# MP3_PCB.net
KiCad netlist of a schematic drawn in Altium Designer
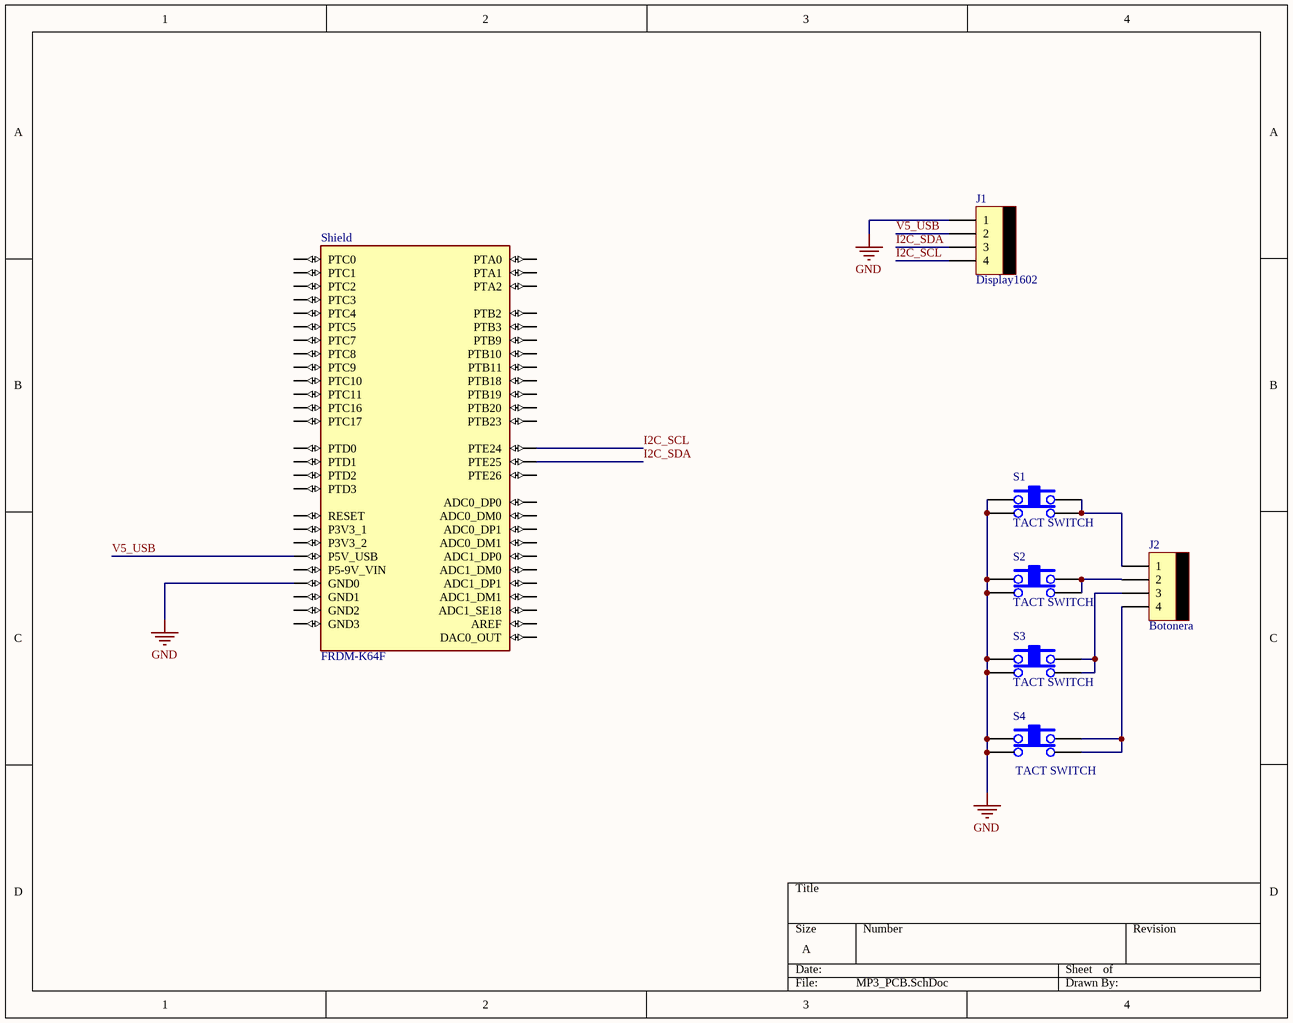
[diagram p0: MP3_PCB.SchDoc]

(export (version "E")
  (design (tool "Eeschema 10.0.6"))
  (components
    (comp (ref "J1") (value "Display1602") (footprint "MOLEX4") (libsource (lib "LIBEBAL") (part "MOLEX4")))
    (comp (ref "J2") (value "Botonera") (footprint "MOLEX4") (libsource (lib "LIBEBAL") (part "MOLEX4")))
    (comp (ref "S1")
      (value "TACT SWITCH")
      (footprint "TACTSWITCH")
      (libsource (lib "LIBEBAL") (part "TACT SWITCH"))
    )
    (comp (ref "S2")
      (value "TACT SWITCH")
      (footprint "TACTSWITCH")
      (libsource (lib "LIBEBAL") (part "TACT SWITCH"))
    )
    (comp (ref "S3")
      (value "TACT SWITCH")
      (footprint "TACTSWITCH")
      (libsource (lib "LIBEBAL") (part "TACT SWITCH"))
    )
    (comp (ref "S4")
      (value "TACT SWITCH")
      (footprint "TACTSWITCH")
      (libsource (lib "LIBEBAL") (part "TACT SWITCH"))
    )
    (comp (ref "Shield")
      (value "FRDM-K64F")
      (footprint "FRDM-K64F")
      (fields (field (name "MF") "NXP USA"))
      (libsource (lib "FRDM-K64F") (part "FRDM-K64F"))
    )
  )
  (nets
    (net (code "1") (name "/I2C_SCL") (class "Default")
      (node (ref "J1") (pin "4") (pinfunction "4_4") (pintype "passive"))
      (node (ref "Shield") (pin "J2-20") (pinfunction "PTE24_J2-20") (pintype "bidirectional"))
    )
    (net (code "2") (name "/I2C_SDA") (class "Default")
      (node (ref "J1") (pin "3") (pinfunction "3_3") (pintype "passive"))
      (node (ref "Shield") (pin "J2-18") (pinfunction "PTE25_J2-18") (pintype "bidirectional"))
    )
    (net (code "3") (name "/V5_USB") (class "Default")
      (node (ref "J1") (pin "2") (pinfunction "2_2") (pintype "passive"))
      (node (ref "Shield") (pin "J3-10") (pinfunction "P5V_USB_J3-10") (pintype "bidirectional"))
    )
    (net (code "4") (name "GND") (class "Default")
      (node (ref "J1") (pin "1") (pinfunction "1_1") (pintype "passive"))
      (node (ref "S1") (pin "1") (pinfunction "1_1") (pintype "passive"))
      (node (ref "S1") (pin "2") (pinfunction "2_2") (pintype "passive"))
      (node (ref "S2") (pin "1") (pinfunction "1_1") (pintype "passive"))
      (node (ref "S2") (pin "2") (pinfunction "2_2") (pintype "passive"))
      (node (ref "S3") (pin "1") (pinfunction "1_1") (pintype "passive"))
      (node (ref "S3") (pin "2") (pinfunction "2_2") (pintype "passive"))
      (node (ref "S4") (pin "1") (pinfunction "1_1") (pintype "passive"))
      (node (ref "S4") (pin "2") (pinfunction "2_2") (pintype "passive"))
      (node (ref "Shield") (pin "J2-3") (pinfunction "GND0_J2-3") (pintype "bidirectional"))
    )
    (net (code "5") (name "Net-(J2-Pad1)") (class "Default")
      (node (ref "J2") (pin "1") (pinfunction "1_1") (pintype "passive"))
      (node (ref "S1") (pin "3") (pinfunction "3_3") (pintype "passive"))
      (node (ref "S1") (pin "4") (pinfunction "4_4") (pintype "passive"))
    )
    (net (code "6") (name "Net-(J2-Pad2)") (class "Default")
      (node (ref "J2") (pin "2") (pinfunction "2_2") (pintype "passive"))
      (node (ref "S2") (pin "3") (pinfunction "3_3") (pintype "passive"))
      (node (ref "S2") (pin "4") (pinfunction "4_4") (pintype "passive"))
    )
    (net (code "7") (name "Net-(J2-Pad3)") (class "Default")
      (node (ref "J2") (pin "3") (pinfunction "3_3") (pintype "passive"))
      (node (ref "S3") (pin "3") (pinfunction "3_3") (pintype "passive"))
      (node (ref "S3") (pin "4") (pinfunction "4_4") (pintype "passive"))
    )
    (net (code "8") (name "Net-(J2-Pad4)") (class "Default")
      (node (ref "J2") (pin "4") (pinfunction "4_4") (pintype "passive"))
      (node (ref "S4") (pin "3") (pinfunction "3_3") (pintype "passive"))
      (node (ref "S4") (pin "4") (pinfunction "4_4") (pintype "passive"))
    )
    (net (code "9") (name "unconnected-(Shield-ADC0_DM0-PadJ2-7)") (class "Default")
      (node (ref "Shield") (pin "J2-7") (pinfunction "ADC0_DM0_J2-7") (pintype "bidirectional"))
    )
    (net (code "10") (name "unconnected-(Shield-ADC0_DM1-PadJ4-3)") (class "Default")
      (node (ref "Shield") (pin "J4-3") (pinfunction "ADC0_DM1_J4-3") (pintype "bidirectional"))
    )
    (net (code "11") (name "unconnected-(Shield-ADC0_DP0-PadJ2-5)") (class "Default")
      (node (ref "Shield") (pin "J2-5") (pinfunction "ADC0_DP0_J2-5") (pintype "bidirectional"))
    )
    (net (code "12") (name "unconnected-(Shield-ADC0_DP1-PadJ4-1)") (class "Default")
      (node (ref "Shield") (pin "J4-1") (pinfunction "ADC0_DP1_J4-1") (pintype "bidirectional"))
    )
    (net (code "13") (name "unconnected-(Shield-ADC1_DM0-PadJ2-13)") (class "Default")
      (node (ref "Shield") (pin "J2-13") (pinfunction "ADC1_DM0_J2-13") (pintype "bidirectional"))
    )
    (net (code "14") (name "unconnected-(Shield-ADC1_DM1-PadJ4-7)") (class "Default")
      (node (ref "Shield") (pin "J4-7") (pinfunction "ADC1_DM1_J4-7") (pintype "bidirectional"))
    )
    (net (code "15") (name "unconnected-(Shield-ADC1_DP0-PadJ2-11)") (class "Default")
      (node (ref "Shield") (pin "J2-11") (pinfunction "ADC1_DP0_J2-11") (pintype "bidirectional"))
    )
    (net (code "16") (name "unconnected-(Shield-ADC1_DP1-PadJ4-5)") (class "Default")
      (node (ref "Shield") (pin "J4-5") (pinfunction "ADC1_DP1_J4-5") (pintype "bidirectional"))
    )
    (net (code "17") (name "unconnected-(Shield-ADC1_SE18-PadJ2-17)") (class "Default")
      (node (ref "Shield") (pin "J2-17") (pinfunction "ADC1_SE18_J2-17") (pintype "bidirectional"))
    )
    (net (code "18") (name "unconnected-(Shield-AREF-PadJ2-16)") (class "Default")
      (node (ref "Shield") (pin "J2-16") (pinfunction "AREF_J2-16") (pintype "bidirectional"))
    )
    (net (code "19") (name "unconnected-(Shield-DAC0_OUT-PadJ4-11)") (class "Default")
      (node (ref "Shield") (pin "J4-11") (pinfunction "DAC0_OUT_J4-11") (pintype "bidirectional"))
    )
    (net (code "20") (name "unconnected-(Shield-GND1-PadJ2-14)") (class "Default")
      (node (ref "Shield") (pin "J2-14") (pinfunction "GND1_J2-14") (pintype "bidirectional"))
    )
    (net (code "21") (name "unconnected-(Shield-GND2-PadJ3-12)") (class "Default")
      (node (ref "Shield") (pin "J3-12") (pinfunction "GND2_J3-12") (pintype "bidirectional"))
    )
    (net (code "22") (name "unconnected-(Shield-GND3-PadJ3-14)") (class "Default")
      (node (ref "Shield") (pin "J3-14") (pinfunction "GND3_J3-14") (pintype "bidirectional"))
    )
    (net (code "23") (name "unconnected-(Shield-P3V3_1-PadJ3-4)") (class "Default")
      (node (ref "Shield") (pin "J3-4") (pinfunction "P3V3_1_J3-4") (pintype "bidirectional"))
    )
    (net (code "24") (name "unconnected-(Shield-P3V3_2-PadJ3-8)") (class "Default")
      (node (ref "Shield") (pin "J3-8") (pinfunction "P3V3_2_J3-8") (pintype "bidirectional"))
    )
    (net (code "25") (name "unconnected-(Shield-P5-9V_VIN-PadJ3-16)") (class "Default")
      (node (ref "Shield") (pin "J3-16") (pinfunction "P5-9V_VIN_J3-16") (pintype "bidirectional"))
    )
    (net (code "26") (name "unconnected-(Shield-PTA0-PadJ2-2)") (class "Default")
      (node (ref "Shield") (pin "J2-2") (pinfunction "PTA0_J2-2") (pintype "bidirectional"))
    )
    (net (code "27") (name "unconnected-(Shield-PTA1-PadJ1-8)") (class "Default")
      (node (ref "Shield") (pin "J1-8") (pinfunction "PTA1_J1-8") (pintype "bidirectional"))
    )
    (net (code "28") (name "unconnected-(Shield-PTA2-PadJ1-12)") (class "Default")
      (node (ref "Shield") (pin "J1-12") (pinfunction "PTA2_J1-12") (pintype "bidirectional"))
    )
    (net (code "29") (name "unconnected-(Shield-PTB2-PadJ4-2)") (class "Default")
      (node (ref "Shield") (pin "J4-2") (pinfunction "PTB2_J4-2") (pintype "bidirectional"))
    )
    (net (code "30") (name "unconnected-(Shield-PTB3-PadJ4-4)") (class "Default")
      (node (ref "Shield") (pin "J4-4") (pinfunction "PTB3_J4-4") (pintype "bidirectional"))
    )
    (net (code "31") (name "unconnected-(Shield-PTB9-PadJ1-6)") (class "Default")
      (node (ref "Shield") (pin "J1-6") (pinfunction "PTB9_J1-6") (pintype "bidirectional"))
    )
    (net (code "32") (name "unconnected-(Shield-PTB10-PadJ4-6)") (class "Default")
      (node (ref "Shield") (pin "J4-6") (pinfunction "PTB10_J4-6") (pintype "bidirectional"))
    )
    (net (code "33") (name "unconnected-(Shield-PTB11-PadJ4-8)") (class "Default")
      (node (ref "Shield") (pin "J4-8") (pinfunction "PTB11_J4-8") (pintype "bidirectional"))
    )
    (net (code "34") (name "unconnected-(Shield-PTB18-PadJ1-1)") (class "Default")
      (node (ref "Shield") (pin "J1-1") (pinfunction "PTB18_J1-1") (pintype "bidirectional"))
    )
    (net (code "35") (name "unconnected-(Shield-PTB19-PadJ1-3)") (class "Default")
      (node (ref "Shield") (pin "J1-3") (pinfunction "PTB19_J1-3") (pintype "bidirectional"))
    )
    (net (code "36") (name "unconnected-(Shield-PTB20-PadJ4-9)") (class "Default")
      (node (ref "Shield") (pin "J4-9") (pinfunction "PTB20_J4-9") (pintype "bidirectional"))
    )
    (net (code "37") (name "unconnected-(Shield-PTB23-PadJ1-10)") (class "Default")
      (node (ref "Shield") (pin "J1-10") (pinfunction "PTB23_J1-10") (pintype "bidirectional"))
    )
    (net (code "38") (name "unconnected-(Shield-PTC0-PadJ1-11)") (class "Default")
      (node (ref "Shield") (pin "J1-11") (pinfunction "PTC0_J1-11") (pintype "bidirectional"))
    )
    (net (code "39") (name "unconnected-(Shield-PTC1-PadJ1-5)") (class "Default")
      (node (ref "Shield") (pin "J1-5") (pinfunction "PTC1_J1-5") (pintype "bidirectional"))
    )
    (net (code "40") (name "unconnected-(Shield-PTC2-PadJ1-14)") (class "Default")
      (node (ref "Shield") (pin "J1-14") (pinfunction "PTC2_J1-14") (pintype "bidirectional"))
    )
    (net (code "41") (name "unconnected-(Shield-PTC3-PadJ1-16)") (class "Default")
      (node (ref "Shield") (pin "J1-16") (pinfunction "PTC3_J1-16") (pintype "bidirectional"))
    )
    (net (code "42") (name "unconnected-(Shield-PTC4-PadJ2-4)") (class "Default")
      (node (ref "Shield") (pin "J2-4") (pinfunction "PTC4_J2-4") (pintype "bidirectional"))
    )
    (net (code "43") (name "unconnected-(Shield-PTC5-PadJ1-15)") (class "Default")
      (node (ref "Shield") (pin "J1-15") (pinfunction "PTC5_J1-15") (pintype "bidirectional"))
    )
    (net (code "44") (name "unconnected-(Shield-PTC7-PadJ1-13)") (class "Default")
      (node (ref "Shield") (pin "J1-13") (pinfunction "PTC7_J1-13") (pintype "bidirectional"))
    )
    (net (code "45") (name "unconnected-(Shield-PTC8-PadJ1-7)") (class "Default")
      (node (ref "Shield") (pin "J1-7") (pinfunction "PTC8_J1-7") (pintype "bidirectional"))
    )
    (net (code "46") (name "unconnected-(Shield-PTC9-PadJ1-9)") (class "Default")
      (node (ref "Shield") (pin "J1-9") (pinfunction "PTC9_J1-9") (pintype "bidirectional"))
    )
    (net (code "47") (name "unconnected-(Shield-PTC10-PadJ4-12)") (class "Default")
      (node (ref "Shield") (pin "J4-12") (pinfunction "PTC10_J4-12") (pintype "bidirectional"))
    )
    (net (code "48") (name "unconnected-(Shield-PTC11-PadJ4-10)") (class "Default")
      (node (ref "Shield") (pin "J4-10") (pinfunction "PTC11_J4-10") (pintype "bidirectional"))
    )
    (net (code "49") (name "unconnected-(Shield-PTC16-PadJ1-2)") (class "Default")
      (node (ref "Shield") (pin "J1-2") (pinfunction "PTC16_J1-2") (pintype "bidirectional"))
    )
    (net (code "50") (name "unconnected-(Shield-PTC17-PadJ1-4)") (class "Default")
      (node (ref "Shield") (pin "J1-4") (pinfunction "PTC17_J1-4") (pintype "bidirectional"))
    )
    (net (code "51") (name "unconnected-(Shield-PTD0-PadJ2-6)") (class "Default")
      (node (ref "Shield") (pin "J2-6") (pinfunction "PTD0_J2-6") (pintype "bidirectional"))
    )
    (net (code "52") (name "unconnected-(Shield-PTD1-PadJ2-12)") (class "Default")
      (node (ref "Shield") (pin "J2-12") (pinfunction "PTD1_J2-12") (pintype "bidirectional"))
    )
    (net (code "53") (name "unconnected-(Shield-PTD2-PadJ2-8)") (class "Default")
      (node (ref "Shield") (pin "J2-8") (pinfunction "PTD2_J2-8") (pintype "bidirectional"))
    )
    (net (code "54") (name "unconnected-(Shield-PTD3-PadJ2-10)") (class "Default")
      (node (ref "Shield") (pin "J2-10") (pinfunction "PTD3_J2-10") (pintype "bidirectional"))
    )
    (net (code "55") (name "unconnected-(Shield-PTE26-PadJ2-1)") (class "Default")
      (node (ref "Shield") (pin "J2-1") (pinfunction "PTE26_J2-1") (pintype "bidirectional"))
    )
    (net (code "56") (name "unconnected-(Shield-RESET-PadJ3-6)") (class "Default")
      (node (ref "Shield") (pin "J3-6") (pinfunction "RESET_J3-6") (pintype "bidirectional"))
    )
  )
)
